# Power.net
KiCad netlist of a schematic drawn in Altium Designer
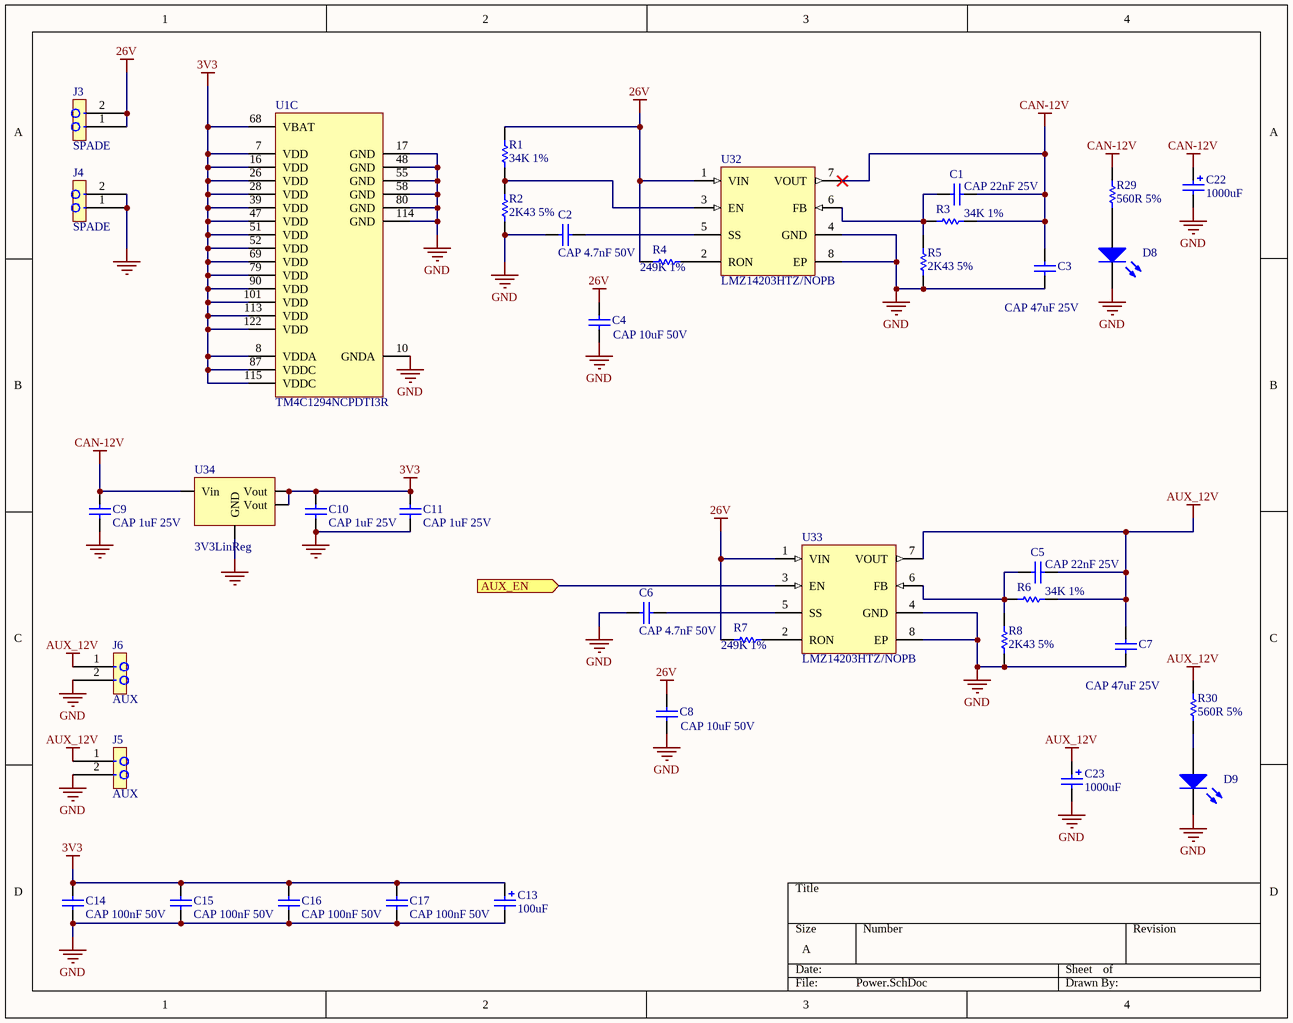
[diagram p0: Power.SchDoc]

(export (version "E")
  (design (tool "Eeschema 10.0.6"))
  (components
    (comp (ref "C1")
      (value "CAP 22nF 25V")
      (footprint "CAPC0805(2012)100_M")
      (description "CAP 22nF 25V Â±5% 0805 (2012 Metric) Thickness 1mm SMD")
      (fields (field (name "TOLERANCE") "Â±5%"))
      (libsource (lib "Altium Content Vault") (part "CMP-1036-04051-1"))
    )
    (comp (ref "C2")
      (value "CAP 4.7nF 50V")
      (footprint "CAPC0603(1608)100_M")
      (description "CAP 4.7nF 50V Â±20% 0603 (1608 Metric) Thickness 1mm SMD")
      (fields (field (name "TOLERANCE") "Â±20%"))
      (libsource (lib "Altium Content Vault") (part "CMP-1035-00333-1"))
    )
    (comp (ref "C3")
      (value "CAP 47uF 25V")
      (footprint "CAPC1206(3216)100_L")
      (description "CAP 47uF 25V Â±0.25pF 1206 (3216 Metric) Thickness 1mm SMD")
      (fields (field (name "TOLERANCE") "Â±0.25pF"))
      (libsource (lib "Altium Content Vault") (part "CMP-1037-00376-1"))
    )
    (comp (ref "C4")
      (value "CAP 10uF 50V")
      (footprint "CAPC1206(3216)190_M")
      (description "CAP 10uF 50V Â±10% 1206 (3216 Metric) Thickness 1.9mm SMD")
      (fields (field (name "TOLERANCE") "Â±10%"))
      (libsource (lib "Altium Content Vault") (part "CMP-1037-04982-1"))
    )
    (comp (ref "C5")
      (value "CAP 22nF 25V")
      (footprint "CAPC0805(2012)100_M")
      (description "CAP 22nF 25V Â±5% 0805 (2012 Metric) Thickness 1mm SMD")
      (fields (field (name "TOLERANCE") "Â±5%"))
      (libsource (lib "Altium Content Vault") (part "CMP-1036-04051-1"))
    )
    (comp (ref "C6")
      (value "CAP 4.7nF 50V")
      (footprint "CAPC0603(1608)100_M")
      (description "CAP 4.7nF 50V Â±20% 0603 (1608 Metric) Thickness 1mm SMD")
      (fields (field (name "TOLERANCE") "Â±20%"))
      (libsource (lib "Altium Content Vault") (part "CMP-1035-00333-1"))
    )
    (comp (ref "C7")
      (value "CAP 47uF 25V")
      (footprint "CAPC1206(3216)100_L")
      (description "CAP 47uF 25V Â±0.25pF 1206 (3216 Metric) Thickness 1mm SMD")
      (fields (field (name "TOLERANCE") "Â±0.25pF"))
      (libsource (lib "Altium Content Vault") (part "CMP-1037-00376-1"))
    )
    (comp (ref "C8")
      (value "CAP 10uF 50V")
      (footprint "CAPC1206(3216)190_M")
      (description "CAP 10uF 50V Â±10% 1206 (3216 Metric) Thickness 1.9mm SMD")
      (fields (field (name "TOLERANCE") "Â±10%"))
      (libsource (lib "Altium Content Vault") (part "CMP-1037-04982-1"))
    )
    (comp (ref "C9")
      (value "CAP 1uF 25V")
      (footprint "CAPC0603(1608)100_M")
      (description "CAP 1uF 25V Â±0.25pF 0603 (1608 Metric) Thickness 1mm SMD")
      (fields (field (name "TOLERANCE") "Â±0.25pF"))
      (libsource (lib "Altium Content Vault") (part "CMP-1035-00037-1"))
    )
    (comp (ref "C10")
      (value "CAP 1uF 25V")
      (footprint "CAPC0603(1608)100_M")
      (description "CAP 1uF 25V Â±0.25pF 0603 (1608 Metric) Thickness 1mm SMD")
      (fields (field (name "TOLERANCE") "Â±0.25pF"))
      (libsource (lib "Altium Content Vault") (part "CMP-1035-00037-1"))
    )
    (comp (ref "C11")
      (value "CAP 1uF 25V")
      (footprint "CAPC0603(1608)100_M")
      (description "CAP 1uF 25V Â±0.25pF 0603 (1608 Metric) Thickness 1mm SMD")
      (fields (field (name "TOLERANCE") "Â±0.25pF"))
      (libsource (lib "Altium Content Vault") (part "CMP-1035-00037-1"))
    )
    (comp (ref "C13")
      (value "100uF")
      (footprint "PANASONIC_C")
      (description "Polarized Capacitor (Surface Mount)")
      (fields (field (name "PUBLISHER") "Altium Limited"))
      (libsource (lib "snarc+") (part "Cap_Polarized_100uF"))
    )
    (comp (ref "C14")
      (value "CAP 100nF 50V")
      (footprint "CAPC0603(1608)100_M")
      (description "CAP 100nF 50V Â±0.1pF 0603 (1608 Metric) Thickness 1mm SMD")
      (fields (field (name "TOLERANCE") "Â±0.1pF"))
      (libsource (lib "Altium Content Vault") (part "CMP-1035-00010-1"))
    )
    (comp (ref "C15")
      (value "CAP 100nF 50V")
      (footprint "CAPC0603(1608)100_M")
      (description "CAP 100nF 50V Â±0.1pF 0603 (1608 Metric) Thickness 1mm SMD")
      (fields (field (name "TOLERANCE") "Â±0.1pF"))
      (libsource (lib "Altium Content Vault") (part "CMP-1035-00010-1"))
    )
    (comp (ref "C16")
      (value "CAP 100nF 50V")
      (footprint "CAPC0603(1608)100_M")
      (description "CAP 100nF 50V Â±0.1pF 0603 (1608 Metric) Thickness 1mm SMD")
      (fields (field (name "TOLERANCE") "Â±0.1pF"))
      (libsource (lib "Altium Content Vault") (part "CMP-1035-00010-1"))
    )
    (comp (ref "C17")
      (value "CAP 100nF 50V")
      (footprint "CAPC0603(1608)100_M")
      (description "CAP 100nF 50V Â±0.1pF 0603 (1608 Metric) Thickness 1mm SMD")
      (fields (field (name "TOLERANCE") "Â±0.1pF"))
      (libsource (lib "Altium Content Vault") (part "CMP-1035-00010-1"))
    )
    (comp (ref "C22")
      (value "1000uF")
      (footprint "PANASONIC_H13")
      (description "Polarized Capacitor (Surface Mount)")
      (fields (field (name "PUBLISHER") "Altium Limited"))
      (libsource (lib "snarc+") (part "Cap_Polarized_1000uF"))
    )
    (comp (ref "C23")
      (value "1000uF")
      (footprint "PANASONIC_H13")
      (description "Polarized Capacitor (Surface Mount)")
      (fields (field (name "PUBLISHER") "Altium Limited"))
      (libsource (lib "snarc+") (part "Cap_Polarized_1000uF"))
    )
    (comp (ref "D8")
      (value "LED")
      (footprint "LED-0603")
      (description "Typical RED, GREEN, YELLOW, AMBER GaAs LED")
      (fields (field (name "PUBLISHER") "Altium Limited"))
      (libsource (lib "HSBNE-Vend") (part "LED"))
    )
    (comp (ref "D9")
      (value "LED")
      (footprint "LED-0603")
      (description "Typical RED, GREEN, YELLOW, AMBER GaAs LED")
      (fields (field (name "PUBLISHER") "Altium Limited"))
      (libsource (lib "HSBNE-Vend") (part "LED"))
    )
    (comp (ref "J3")
      (value "SPADE")
      (footprint "SPADE-6.35-RA")
      (description "6.35mm right-angle 90° male spade terminal PCB mount")
      (libsource (lib "") (part "CON2_1"))
    )
    (comp (ref "J4")
      (value "SPADE")
      (footprint "SPADE-6.35-RA")
      (description "6.35mm right-angle 90° male spade terminal PCB mount")
      (libsource (lib "") (part "CON2_1"))
    )
    (comp (ref "J5")
      (value "AUX")
      (footprint "M5569-2")
      (description "6.35mm right-angle 90° male spade terminal PCB mount")
      (libsource (lib "HSBNE-Vend") (part "CON2"))
    )
    (comp (ref "J6")
      (value "AUX")
      (footprint "M5569-2")
      (description "6.35mm right-angle 90° male spade terminal PCB mount")
      (libsource (lib "HSBNE-Vend") (part "CON2"))
    )
    (comp (ref "R1")
      (value "34K 1%")
      (footprint "RESC0603(1608)_M")
      (description "34K 0.1W 1% 0603 (1608 Metric)  SMD")
      (fields (field (name "TOLERANCE") "1 %") (field (name "POWER") "0.1 W"))
      (libsource (lib "Altium Content Vault") (part "CMP-1012-00682-1"))
    )
    (comp (ref "R2")
      (value "2K43 5%")
      (footprint "RESC0603(1608)_M")
      (description "2K43 0.1W 5% 0603 (1608 Metric)  SMD")
      (fields (field (name "TOLERANCE") "5 %") (field (name "POWER") "0.1 W"))
      (libsource (lib "Altium Content Vault") (part "CMP-1012-00083-1"))
    )
    (comp (ref "R3")
      (value "34K 1%")
      (footprint "RESC0603(1608)_M")
      (description "34K 0.1W 1% 0603 (1608 Metric)  SMD")
      (fields (field (name "TOLERANCE") "1 %") (field (name "POWER") "0.1 W"))
      (libsource (lib "Altium Content Vault") (part "CMP-1012-00682-1"))
    )
    (comp (ref "R4")
      (value "249K 1%")
      (footprint "RESC0603(1608)_M")
      (description "249K 0.1W 1% 0603 (1608 Metric)  SMD")
      (fields (field (name "POWER") "0.1 W") (field (name "TOLERANCE") "1 %"))
      (libsource (lib "Altium Content Vault") (part "CMP-1012-00779-1"))
    )
    (comp (ref "R5")
      (value "2K43 5%")
      (footprint "RESC0603(1608)_M")
      (description "2K43 0.1W 5% 0603 (1608 Metric)  SMD")
      (fields (field (name "TOLERANCE") "5 %") (field (name "POWER") "0.1 W"))
      (libsource (lib "Altium Content Vault") (part "CMP-1012-00083-1"))
    )
    (comp (ref "R6")
      (value "34K 1%")
      (footprint "RESC0603(1608)_M")
      (description "34K 0.1W 1% 0603 (1608 Metric)  SMD")
      (fields (field (name "TOLERANCE") "1 %") (field (name "POWER") "0.1 W"))
      (libsource (lib "Altium Content Vault") (part "CMP-1012-00682-1"))
    )
    (comp (ref "R7")
      (value "249K 1%")
      (footprint "RESC0603(1608)_M")
      (description "249K 0.1W 1% 0603 (1608 Metric)  SMD")
      (fields (field (name "POWER") "0.1 W") (field (name "TOLERANCE") "1 %"))
      (libsource (lib "Altium Content Vault") (part "CMP-1012-00779-1"))
    )
    (comp (ref "R8")
      (value "2K43 5%")
      (footprint "RESC0603(1608)_M")
      (description "2K43 0.1W 5% 0603 (1608 Metric)  SMD")
      (fields (field (name "TOLERANCE") "5 %") (field (name "POWER") "0.1 W"))
      (libsource (lib "Altium Content Vault") (part "CMP-1012-00083-1"))
    )
    (comp (ref "R29")
      (value "560R 5%")
      (footprint "RESC0603(1608)_M")
      (description "560R 0.1W 5% 0603 (1608 Metric)  SMD")
      (fields (field (name "TOLERANCE") "5 %") (field (name "POWER") "0.1 W"))
      (libsource (lib "Altium Content Vault") (part "RES"))
    )
    (comp (ref "R30")
      (value "560R 5%")
      (footprint "RESC0603(1608)_M")
      (description "560R 0.1W 5% 0603 (1608 Metric)  SMD")
      (fields (field (name "TOLERANCE") "5 %") (field (name "POWER") "0.1 W"))
      (libsource (lib "Altium Content Vault") (part "RES"))
    )
    (comp (ref "U1")
      (value "TM4C1294NCPDTI3R")
      (footprint "TI-PDT128_M")
      (fields (field (name "MANUFACTURER") "Texas Instruments"))
      (libsource (lib "Altium Inc") (part "TI-TM4C1294NCPDT-128"))
    )
    (comp (ref "U32")
      (value "LMZ14203HTZ/NOPB")
      (footprint "TZA07A_V")
      (fields (field (name "MANUFACTURER") "National Semiconductor"))
      (libsource (lib "Altium Content Vault") (part "PM-REG-LMZ12003-8"))
    )
    (comp (ref "U33")
      (value "LMZ14203HTZ/NOPB")
      (footprint "TZA07A_V")
      (fields (field (name "MANUFACTURER") "National Semiconductor"))
      (libsource (lib "Altium Content Vault") (part "PM-REG-LMZ12003-8"))
    )
    (comp (ref "U34")
      (value "3V3LinReg")
      (footprint "SOT-223")
      (description "Reg 1A 3V3 OUT SIP VERT")
      (libsource (lib "HSBNE-Vend") (part "AZ1117EH"))
    )
  )
  (nets
    (net (code "1") (name "/AUX_EN") (class "Default")
      (node (ref "U33") (pin "3") (pinfunction "EN_3") (pintype "input"))
    )
    (net (code "2") (name "3V3") (class "Default")
      (node (ref "C10") (pin "2") (pinfunction "2_2") (pintype "passive"))
      (node (ref "C11") (pin "2") (pinfunction "2_2") (pintype "passive"))
      (node (ref "C13") (pin "+") (pinfunction "+_+") (pintype "passive"))
      (node (ref "C14") (pin "2") (pinfunction "2_2") (pintype "passive"))
      (node (ref "C15") (pin "2") (pinfunction "2_2") (pintype "passive"))
      (node (ref "C16") (pin "2") (pinfunction "2_2") (pintype "passive"))
      (node (ref "C17") (pin "2") (pinfunction "2_2") (pintype "passive"))
      (node (ref "U1") (pin "101") (pinfunction "VDD_101") (pintype "power_in"))
      (node (ref "U1") (pin "113") (pinfunction "VDD_113") (pintype "power_in"))
      (node (ref "U1") (pin "115") (pinfunction "VDDC_115") (pintype "power_in"))
      (node (ref "U1") (pin "122") (pinfunction "VDD_122") (pintype "power_in"))
      (node (ref "U1") (pin "16") (pinfunction "VDD_16") (pintype "power_in"))
      (node (ref "U1") (pin "26") (pinfunction "VDD_26") (pintype "power_in"))
      (node (ref "U1") (pin "28") (pinfunction "VDD_28") (pintype "power_in"))
      (node (ref "U1") (pin "39") (pinfunction "VDD_39") (pintype "power_in"))
      (node (ref "U1") (pin "47") (pinfunction "VDD_47") (pintype "power_in"))
      (node (ref "U1") (pin "51") (pinfunction "VDD_51") (pintype "power_in"))
      (node (ref "U1") (pin "52") (pinfunction "VDD_52") (pintype "power_in"))
      (node (ref "U1") (pin "68") (pinfunction "VBAT_68") (pintype "power_in"))
      (node (ref "U1") (pin "69") (pinfunction "VDD_69") (pintype "power_in"))
      (node (ref "U1") (pin "7") (pinfunction "VDD_7") (pintype "power_in"))
      (node (ref "U1") (pin "79") (pinfunction "VDD_79") (pintype "power_in"))
      (node (ref "U1") (pin "8") (pinfunction "VDDA_8") (pintype "power_in"))
      (node (ref "U1") (pin "87") (pinfunction "VDDC_87") (pintype "power_in"))
      (node (ref "U1") (pin "90") (pinfunction "VDD_90") (pintype "power_in"))
      (node (ref "U34") (pin "2") (pinfunction "Vout_2") (pintype "power_in"))
      (node (ref "U34") (pin "4") (pinfunction "Vout_4") (pintype "power_in"))
    )
    (net (code "3") (name "26V") (class "Default")
      (node (ref "C4") (pin "1") (pinfunction "1_1") (pintype "passive"))
      (node (ref "C8") (pin "1") (pinfunction "1_1") (pintype "passive"))
      (node (ref "J3") (pin "1") (pintype "passive"))
      (node (ref "J3") (pin "2") (pintype "passive"))
      (node (ref "R1") (pin "2") (pinfunction "2_2") (pintype "passive"))
      (node (ref "R4") (pin "1") (pinfunction "1_1") (pintype "passive"))
      (node (ref "R7") (pin "1") (pinfunction "1_1") (pintype "passive"))
      (node (ref "U32") (pin "1") (pinfunction "VIN_1") (pintype "input"))
      (node (ref "U33") (pin "1") (pinfunction "VIN_1") (pintype "input"))
    )
    (net (code "4") (name "AUX_12V") (class "Default")
      (node (ref "C23") (pin "+") (pinfunction "+_+") (pintype "passive"))
      (node (ref "C5") (pin "2") (pinfunction "2_2") (pintype "passive"))
      (node (ref "C7") (pin "1") (pinfunction "1_1") (pintype "passive"))
      (node (ref "J5") (pin "1") (pintype "passive"))
      (node (ref "J6") (pin "1") (pintype "passive"))
      (node (ref "R30") (pin "2") (pinfunction "2_2") (pintype "passive"))
      (node (ref "R6") (pin "2") (pinfunction "2_2") (pintype "passive"))
      (node (ref "U33") (pin "7") (pinfunction "VOUT_7") (pintype "output"))
    )
    (net (code "5") (name "CAN-12V") (class "Default")
      (node (ref "C1") (pin "2") (pinfunction "2_2") (pintype "passive"))
      (node (ref "C22") (pin "+") (pinfunction "+_+") (pintype "passive"))
      (node (ref "C3") (pin "1") (pinfunction "1_1") (pintype "passive"))
      (node (ref "C9") (pin "2") (pinfunction "2_2") (pintype "passive"))
      (node (ref "R29") (pin "2") (pinfunction "2_2") (pintype "passive"))
      (node (ref "R3") (pin "2") (pinfunction "2_2") (pintype "passive"))
      (node (ref "U32") (pin "7") (pinfunction "VOUT_7") (pintype "output"))
      (node (ref "U34") (pin "3") (pinfunction "Vin_3") (pintype "power_in"))
    )
    (net (code "6") (name "GND") (class "Default")
      (node (ref "C10") (pin "1") (pinfunction "1_1") (pintype "passive"))
      (node (ref "C11") (pin "1") (pinfunction "1_1") (pintype "passive"))
      (node (ref "C13") (pin "-") (pinfunction "-_-") (pintype "passive"))
      (node (ref "C14") (pin "1") (pinfunction "1_1") (pintype "passive"))
      (node (ref "C15") (pin "1") (pinfunction "1_1") (pintype "passive"))
      (node (ref "C16") (pin "1") (pinfunction "1_1") (pintype "passive"))
      (node (ref "C17") (pin "1") (pinfunction "1_1") (pintype "passive"))
      (node (ref "C2") (pin "1") (pinfunction "1_1") (pintype "passive"))
      (node (ref "C22") (pin "-") (pinfunction "-_-") (pintype "passive"))
      (node (ref "C23") (pin "-") (pinfunction "-_-") (pintype "passive"))
      (node (ref "C3") (pin "2") (pinfunction "2_2") (pintype "passive"))
      (node (ref "C4") (pin "2") (pinfunction "2_2") (pintype "passive"))
      (node (ref "C6") (pin "1") (pinfunction "1_1") (pintype "passive"))
      (node (ref "C7") (pin "2") (pinfunction "2_2") (pintype "passive"))
      (node (ref "C8") (pin "2") (pinfunction "2_2") (pintype "passive"))
      (node (ref "C9") (pin "1") (pinfunction "1_1") (pintype "passive"))
      (node (ref "D8") (pin "2") (pinfunction "K_2") (pintype "passive"))
      (node (ref "D9") (pin "2") (pinfunction "K_2") (pintype "passive"))
      (node (ref "J4") (pin "1") (pintype "passive"))
      (node (ref "J4") (pin "2") (pintype "passive"))
      (node (ref "J5") (pin "2") (pintype "passive"))
      (node (ref "J6") (pin "2") (pintype "passive"))
      (node (ref "R2") (pin "1") (pinfunction "1_1") (pintype "passive"))
      (node (ref "R5") (pin "1") (pinfunction "1_1") (pintype "passive"))
      (node (ref "R8") (pin "1") (pinfunction "1_1") (pintype "passive"))
      (node (ref "U1") (pin "10") (pinfunction "GNDA_10") (pintype "power_in"))
      (node (ref "U1") (pin "114") (pinfunction "GND_114") (pintype "power_in"))
      (node (ref "U1") (pin "17") (pinfunction "GND_17") (pintype "power_in"))
      (node (ref "U1") (pin "48") (pinfunction "GND_48") (pintype "power_in"))
      (node (ref "U1") (pin "55") (pinfunction "GND_55") (pintype "power_in"))
      (node (ref "U1") (pin "58") (pinfunction "GND_58") (pintype "power_in"))
      (node (ref "U1") (pin "80") (pinfunction "GND_80") (pintype "power_in"))
      (node (ref "U32") (pin "4") (pinfunction "GND_4") (pintype "power_in"))
      (node (ref "U32") (pin "8") (pinfunction "EP_8") (pintype "passive"))
      (node (ref "U33") (pin "4") (pinfunction "GND_4") (pintype "power_in"))
      (node (ref "U33") (pin "8") (pinfunction "EP_8") (pintype "passive"))
      (node (ref "U34") (pin "1") (pinfunction "GND_1") (pintype "power_in"))
    )
    (net (code "7") (name "Net-(D8-A)") (class "Default")
      (node (ref "D8") (pin "1") (pinfunction "A_1") (pintype "passive"))
      (node (ref "R29") (pin "1") (pinfunction "1_1") (pintype "passive"))
    )
    (net (code "8") (name "Net-(D9-A)") (class "Default")
      (node (ref "D9") (pin "1") (pinfunction "A_1") (pintype "passive"))
      (node (ref "R30") (pin "1") (pinfunction "1_1") (pintype "passive"))
    )
    (net (code "9") (name "Net-(U32-EN)") (class "Default")
      (node (ref "R1") (pin "1") (pinfunction "1_1") (pintype "passive"))
      (node (ref "R2") (pin "2") (pinfunction "2_2") (pintype "passive"))
      (node (ref "U32") (pin "3") (pinfunction "EN_3") (pintype "input"))
    )
    (net (code "10") (name "Net-(U32-FB)") (class "Default")
      (node (ref "C1") (pin "1") (pinfunction "1_1") (pintype "passive"))
      (node (ref "R3") (pin "1") (pinfunction "1_1") (pintype "passive"))
      (node (ref "R5") (pin "2") (pinfunction "2_2") (pintype "passive"))
      (node (ref "U32") (pin "6") (pinfunction "FB_6") (pintype "input"))
    )
    (net (code "11") (name "Net-(U32-RON)") (class "Default")
      (node (ref "R4") (pin "2") (pinfunction "2_2") (pintype "passive"))
      (node (ref "U32") (pin "2") (pinfunction "RON_2") (pintype "passive"))
    )
    (net (code "12") (name "Net-(U32-SS)") (class "Default")
      (node (ref "C2") (pin "2") (pinfunction "2_2") (pintype "passive"))
      (node (ref "U32") (pin "5") (pinfunction "SS_5") (pintype "passive"))
    )
    (net (code "13") (name "Net-(U33-FB)") (class "Default")
      (node (ref "C5") (pin "1") (pinfunction "1_1") (pintype "passive"))
      (node (ref "R6") (pin "1") (pinfunction "1_1") (pintype "passive"))
      (node (ref "R8") (pin "2") (pinfunction "2_2") (pintype "passive"))
      (node (ref "U33") (pin "6") (pinfunction "FB_6") (pintype "input"))
    )
    (net (code "14") (name "Net-(U33-RON)") (class "Default")
      (node (ref "R7") (pin "2") (pinfunction "2_2") (pintype "passive"))
      (node (ref "U33") (pin "2") (pinfunction "RON_2") (pintype "passive"))
    )
    (net (code "15") (name "Net-(U33-SS)") (class "Default")
      (node (ref "C6") (pin "2") (pinfunction "2_2") (pintype "passive"))
      (node (ref "U33") (pin "5") (pinfunction "SS_5") (pintype "passive"))
    )
  )
)
